# untitled.net
KiCad netlist of a schematic drawn in EAGLE
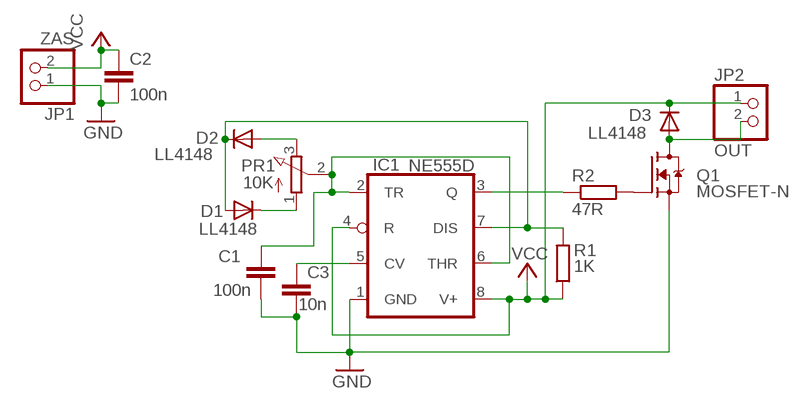
[diagram p0: schematic, sheet 1]

(export (version "E")
  (design (tool "Eeschema 10.0.6"))
  (components
    (comp (ref "C1")
      (value "100n")
      (footprint "eagle-import:C0603")
      (libsource (lib "eagle-import") (part "C-EUC0603"))
    )
    (comp (ref "C2")
      (value "100n")
      (footprint "eagle-import:C1206")
      (libsource (lib "eagle-import") (part "C-EUC1206"))
    )
    (comp (ref "C3")
      (value "10n")
      (footprint "eagle-import:C0603")
      (libsource (lib "eagle-import") (part "C-EUC0603"))
    )
    (comp (ref "D1")
      (value "LL4148")
      (footprint "eagle-import:MINIMELF")
      (libsource (lib "eagle-import") (part "DIODE-MINIMELF"))
    )
    (comp (ref "D2")
      (value "LL4148")
      (footprint "eagle-import:MINIMELF")
      (libsource (lib "eagle-import") (part "DIODE-MINIMELF"))
    )
    (comp (ref "D3")
      (value "LL4148")
      (footprint "eagle-import:MINIMELF")
      (libsource (lib "eagle-import") (part "DIODE-MINIMELF"))
    )
    (comp (ref "IC1")
      (value "NE555D")
      (footprint "eagle-import:SO08")
      (libsource (lib "eagle-import") (part "555DNE"))
    )
    (comp (ref "JP1")
      (value "ZAS")
      (footprint "eagle-import:1X02")
      (libsource (lib "eagle-import") (part "PINHD-1X2"))
    )
    (comp (ref "JP2")
      (value "OUT")
      (footprint "eagle-import:1X02")
      (libsource (lib "eagle-import") (part "PINHD-1X2"))
    )
    (comp (ref "PR1")
      (value "10K")
      (footprint "eagle-import:3RP_1610N")
      (libsource (lib "eagle-import") (part "3RP/1610N"))
    )
    (comp (ref "Q1")
      (value "MOSFET-N")
      (footprint "eagle-import:TO252")
      (libsource (lib "eagle-import") (part "MOSFET-N"))
    )
    (comp (ref "R1")
      (value "1K")
      (footprint "eagle-import:R0603")
      (libsource (lib "eagle-import") (part "R-EU_R0603"))
    )
    (comp (ref "R2")
      (value "47R")
      (footprint "eagle-import:R0603")
      (libsource (lib "eagle-import") (part "R-EU_R0603"))
    )
  )
  (nets
    (net (code "1") (name "GND") (class "Default")
      (node (ref "C1") (pin "2") (pinfunction "2_2") (pintype "passive"))
      (node (ref "C2") (pin "2") (pinfunction "2_2") (pintype "passive"))
      (node (ref "C3") (pin "2") (pinfunction "2_2") (pintype "passive"))
      (node (ref "IC1") (pin "1") (pinfunction "GND_1") (pintype "power_in"))
      (node (ref "JP1") (pin "1") (pinfunction "1_1") (pintype "passive"))
      (node (ref "Q1") (pin "2") (pinfunction "S_2") (pintype "passive"))
    )
    (net (code "2") (name "Net-(IC1-CV)") (class "Default")
      (node (ref "C3") (pin "1") (pinfunction "1_1") (pintype "passive"))
      (node (ref "IC1") (pin "5") (pinfunction "CV_5") (pintype "input"))
    )
    (net (code "3") (name "Net-(IC1-DIS)") (class "Default")
      (node (ref "D1") (pin "A") (pinfunction "A_A") (pintype "passive"))
      (node (ref "D2") (pin "C") (pinfunction "C_C") (pintype "passive"))
      (node (ref "IC1") (pin "7") (pinfunction "DIS_7") (pintype "input"))
      (node (ref "R1") (pin "2") (pinfunction "2_2") (pintype "passive"))
    )
    (net (code "4") (name "Net-(IC1-Q)") (class "Default")
      (node (ref "IC1") (pin "3") (pinfunction "Q_3") (pintype "output"))
      (node (ref "R2") (pin "1") (pinfunction "1_1") (pintype "passive"))
    )
    (net (code "5") (name "Net-(IC1-THR)") (class "Default")
      (node (ref "C1") (pin "1") (pinfunction "1_1") (pintype "passive"))
      (node (ref "IC1") (pin "2") (pinfunction "TR_2") (pintype "input"))
      (node (ref "IC1") (pin "6") (pinfunction "THR_6") (pintype "input"))
      (node (ref "PR1") (pin "2") (pinfunction "S_2") (pintype "passive"))
    )
    (net (code "6") (name "Net-(PR1-A)") (class "Default")
      (node (ref "D1") (pin "C") (pinfunction "C_C") (pintype "passive"))
      (node (ref "PR1") (pin "1") (pinfunction "A_1") (pintype "passive"))
    )
    (net (code "7") (name "Net-(PR1-E)") (class "Default")
      (node (ref "D2") (pin "A") (pinfunction "A_A") (pintype "passive"))
      (node (ref "PR1") (pin "3") (pinfunction "E_3") (pintype "passive"))
    )
    (net (code "8") (name "Net-(Q1-D)") (class "Default")
      (node (ref "D3") (pin "A") (pinfunction "A_A") (pintype "passive"))
      (node (ref "JP2") (pin "2") (pinfunction "2_2") (pintype "passive"))
      (node (ref "Q1") (pin "3") (pinfunction "D_3") (pintype "passive"))
    )
    (net (code "9") (name "Net-(Q1-G)") (class "Default")
      (node (ref "Q1") (pin "1") (pinfunction "G_1") (pintype "passive"))
      (node (ref "R2") (pin "2") (pinfunction "2_2") (pintype "passive"))
    )
    (net (code "10") (name "VCC") (class "Default")
      (node (ref "C2") (pin "1") (pinfunction "1_1") (pintype "passive"))
      (node (ref "D3") (pin "C") (pinfunction "C_C") (pintype "passive"))
      (node (ref "IC1") (pin "4") (pinfunction "R_4") (pintype "input"))
      (node (ref "IC1") (pin "8") (pinfunction "V+_8") (pintype "power_in"))
      (node (ref "JP1") (pin "2") (pinfunction "2_2") (pintype "passive"))
      (node (ref "JP2") (pin "1") (pinfunction "1_1") (pintype "passive"))
      (node (ref "R1") (pin "1") (pinfunction "1_1") (pintype "passive"))
    )
  )
)
